# ESP32E_Double_RGB_RevA.net
KiCad netlist of a schematic drawn in EAGLE
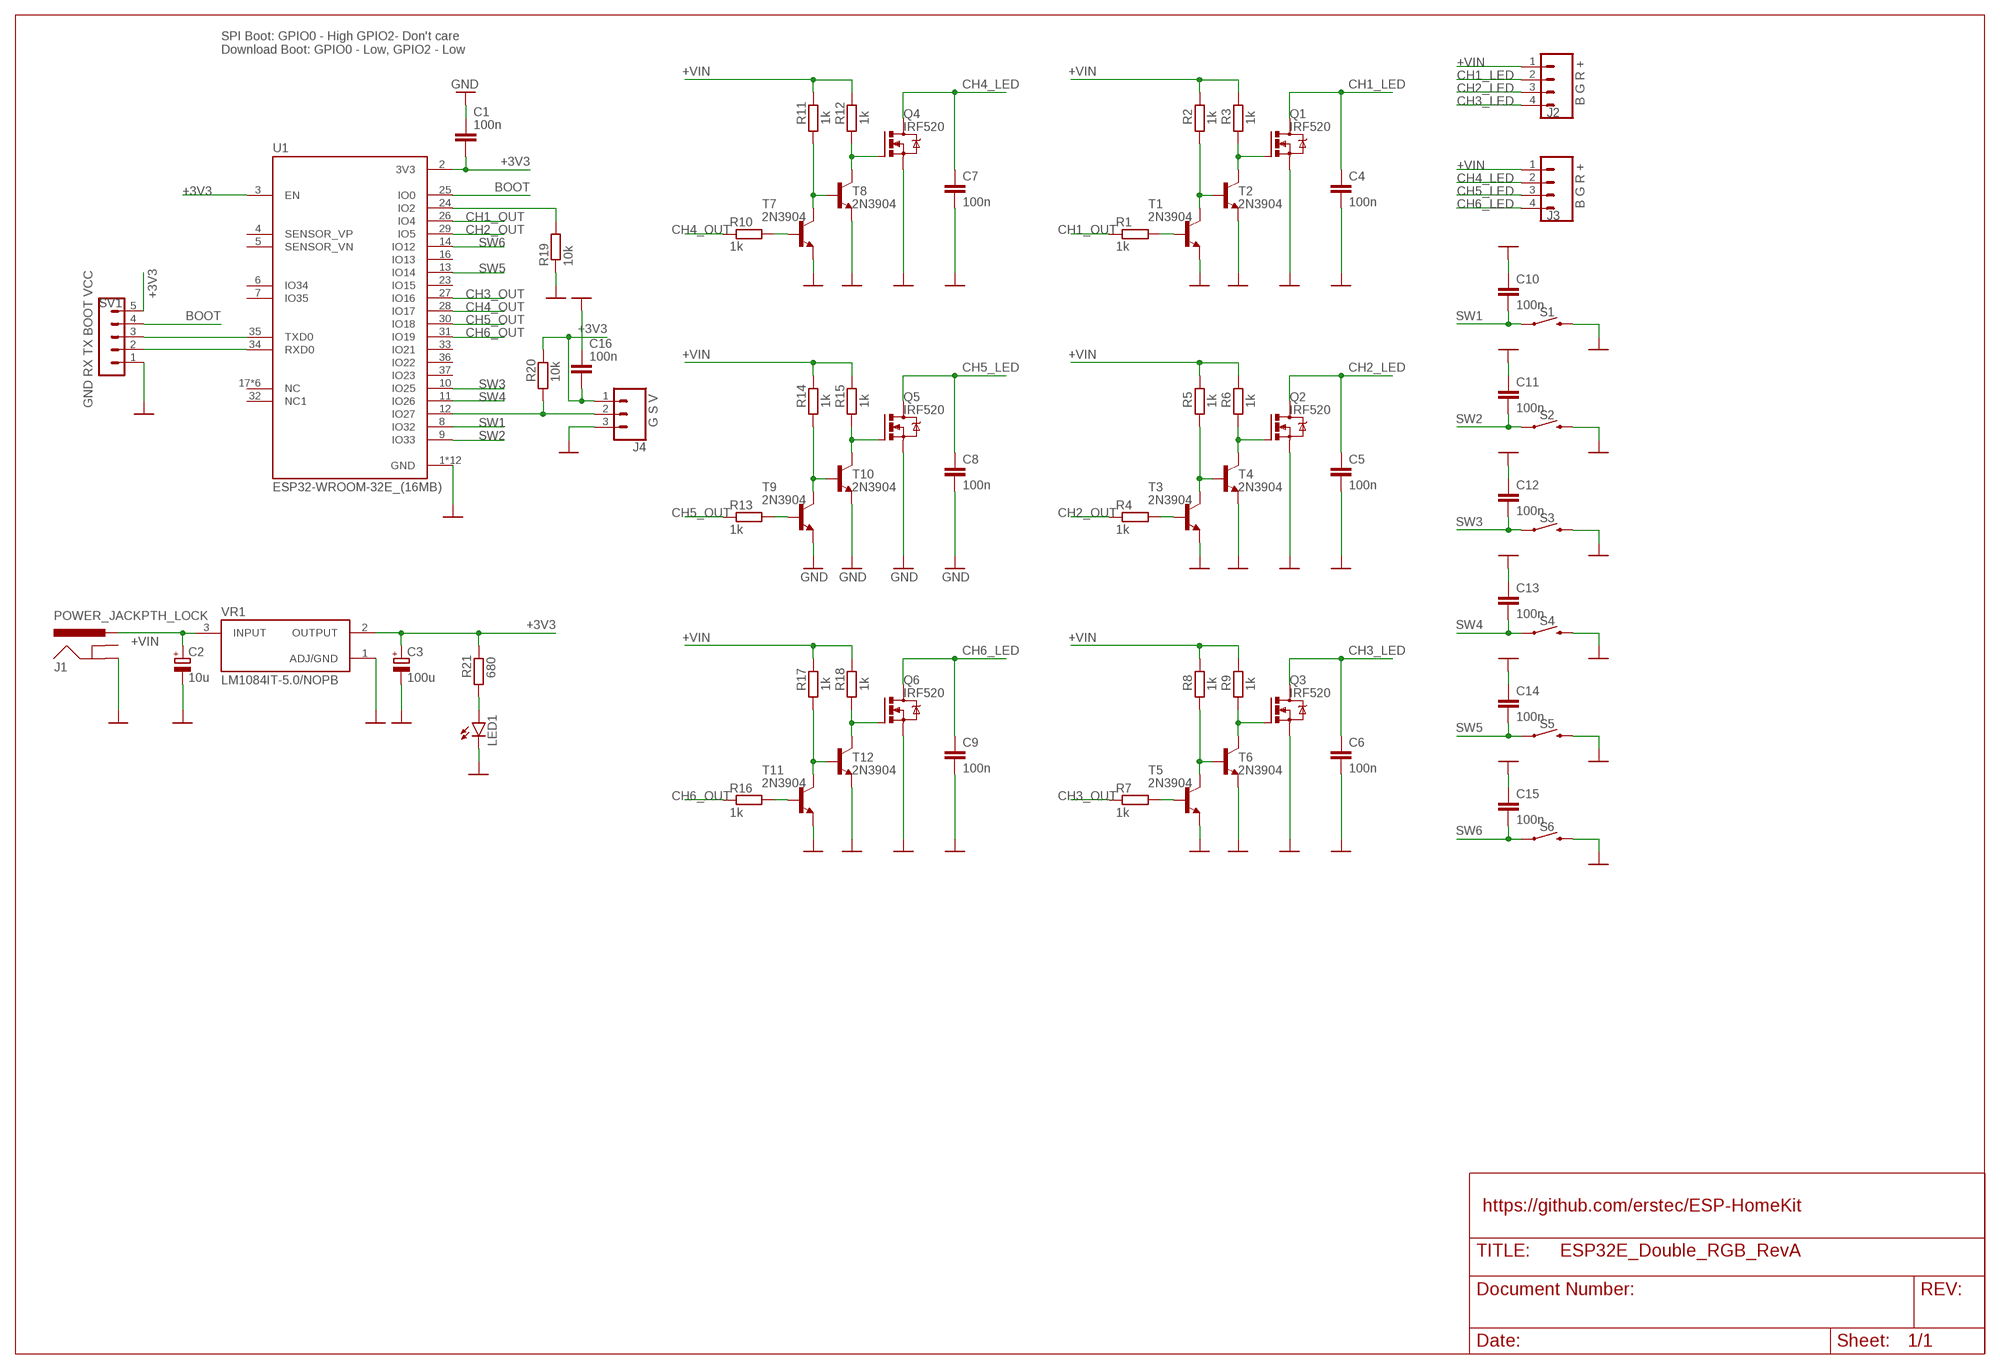
[diagram p0: schematic, sheet 1]

(export (version "E")
  (design (tool "Eeschema 10.0.6"))
  (components
    (comp (ref "C1")
      (value "100n")
      (footprint "eagle-import:C025-024X044")
      (libsource (lib "eagle-import") (part "C-EU025-024X044"))
    )
    (comp (ref "C2")
      (value "10u")
      (footprint "eagle-import:E2,5-6E")
      (libsource (lib "eagle-import") (part "CPOL-EUE2,5-6E"))
    )
    (comp (ref "C3")
      (value "100u")
      (footprint "eagle-import:E2,5-6")
      (libsource (lib "eagle-import") (part "CPOL-EUE2.5-6"))
    )
    (comp (ref "C4")
      (value "100n")
      (footprint "eagle-import:C025-024X044")
      (libsource (lib "eagle-import") (part "C-EU025-024X044"))
    )
    (comp (ref "C5")
      (value "100n")
      (footprint "eagle-import:C025-024X044")
      (libsource (lib "eagle-import") (part "C-EU025-024X044"))
    )
    (comp (ref "C6")
      (value "100n")
      (footprint "eagle-import:C025-024X044")
      (libsource (lib "eagle-import") (part "C-EU025-024X044"))
    )
    (comp (ref "C7")
      (value "100n")
      (footprint "eagle-import:C025-024X044")
      (libsource (lib "eagle-import") (part "C-EU025-024X044"))
    )
    (comp (ref "C8")
      (value "100n")
      (footprint "eagle-import:C025-024X044")
      (libsource (lib "eagle-import") (part "C-EU025-024X044"))
    )
    (comp (ref "C9")
      (value "100n")
      (footprint "eagle-import:C025-024X044")
      (libsource (lib "eagle-import") (part "C-EU025-024X044"))
    )
    (comp (ref "C10")
      (value "100n")
      (footprint "eagle-import:C025-024X044")
      (libsource (lib "eagle-import") (part "C-EU025-024X044"))
    )
    (comp (ref "C11")
      (value "100n")
      (footprint "eagle-import:C025-024X044")
      (libsource (lib "eagle-import") (part "C-EU025-024X044"))
    )
    (comp (ref "C12")
      (value "100n")
      (footprint "eagle-import:C025-024X044")
      (libsource (lib "eagle-import") (part "C-EU025-024X044"))
    )
    (comp (ref "C13")
      (value "100n")
      (footprint "eagle-import:C025-024X044")
      (libsource (lib "eagle-import") (part "C-EU025-024X044"))
    )
    (comp (ref "C14")
      (value "100n")
      (footprint "eagle-import:C025-024X044")
      (libsource (lib "eagle-import") (part "C-EU025-024X044"))
    )
    (comp (ref "C15")
      (value "100n")
      (footprint "eagle-import:C025-024X044")
      (libsource (lib "eagle-import") (part "C-EU025-024X044"))
    )
    (comp (ref "C16")
      (value "100n")
      (footprint "eagle-import:C025-024X044")
      (libsource (lib "eagle-import") (part "C-EU025-024X044"))
    )
    (comp (ref "J1")
      (value "POWER_JACKPTH_LOCK")
      (footprint "eagle-import:POWER_JACK_PTH_LOCK")
      (libsource (lib "eagle-import") (part "POWER_JACKPTH_LOCK"))
    )
    (comp (ref "J2")
      (value "B G R +")
      (footprint "eagle-import:SCREWTERMINAL-3.5MM-4_LOCK")
      (libsource (lib "eagle-import") (part "CONN_04SCREW_LOCK"))
    )
    (comp (ref "J3")
      (value "B G R +")
      (footprint "eagle-import:SCREWTERMINAL-3.5MM-4_LOCK")
      (libsource (lib "eagle-import") (part "CONN_04SCREW_LOCK"))
    )
    (comp (ref "J4")
      (value "G S V")
      (footprint "eagle-import:SCREWTERMINAL-3.5MM-3_LOCK.007S")
      (libsource (lib "eagle-import") (part "CONN_03SCREW_LOCK"))
    )
    (comp (ref "LED1")
      (value "LED5MM")
      (footprint "eagle-import:LED5MM")
      (libsource (lib "eagle-import") (part "LED5MM"))
    )
    (comp (ref "Q1")
      (value "IRF520")
      (footprint "eagle-import:TO220BV")
      (libsource (lib "eagle-import") (part "IRF520"))
    )
    (comp (ref "Q2")
      (value "IRF520")
      (footprint "eagle-import:TO220BV")
      (libsource (lib "eagle-import") (part "IRF520"))
    )
    (comp (ref "Q3")
      (value "IRF520")
      (footprint "eagle-import:TO220BV")
      (libsource (lib "eagle-import") (part "IRF520"))
    )
    (comp (ref "Q4")
      (value "IRF520")
      (footprint "eagle-import:TO220BV")
      (libsource (lib "eagle-import") (part "IRF520"))
    )
    (comp (ref "Q5")
      (value "IRF520")
      (footprint "eagle-import:TO220BV")
      (libsource (lib "eagle-import") (part "IRF520"))
    )
    (comp (ref "Q6")
      (value "IRF520")
      (footprint "eagle-import:TO220BV")
      (libsource (lib "eagle-import") (part "IRF520"))
    )
    (comp (ref "R1")
      (value "1k")
      (footprint "eagle-import:0207_10")
      (libsource (lib "eagle-import") (part "R-EU_0207/10"))
    )
    (comp (ref "R2")
      (value "1k")
      (footprint "eagle-import:0207_10")
      (libsource (lib "eagle-import") (part "R-EU_0207/10"))
    )
    (comp (ref "R3")
      (value "1k")
      (footprint "eagle-import:0207_10")
      (libsource (lib "eagle-import") (part "R-EU_0207/10"))
    )
    (comp (ref "R4")
      (value "1k")
      (footprint "eagle-import:0207_10")
      (libsource (lib "eagle-import") (part "R-EU_0207/10"))
    )
    (comp (ref "R5")
      (value "1k")
      (footprint "eagle-import:0207_10")
      (libsource (lib "eagle-import") (part "R-EU_0207/10"))
    )
    (comp (ref "R6")
      (value "1k")
      (footprint "eagle-import:0207_10")
      (libsource (lib "eagle-import") (part "R-EU_0207/10"))
    )
    (comp (ref "R7")
      (value "1k")
      (footprint "eagle-import:0207_10")
      (libsource (lib "eagle-import") (part "R-EU_0207/10"))
    )
    (comp (ref "R8")
      (value "1k")
      (footprint "eagle-import:0207_10")
      (libsource (lib "eagle-import") (part "R-EU_0207/10"))
    )
    (comp (ref "R9")
      (value "1k")
      (footprint "eagle-import:0207_10")
      (libsource (lib "eagle-import") (part "R-EU_0207/10"))
    )
    (comp (ref "R10")
      (value "1k")
      (footprint "eagle-import:0207_10")
      (libsource (lib "eagle-import") (part "R-EU_0207/10"))
    )
    (comp (ref "R11")
      (value "1k")
      (footprint "eagle-import:0207_10")
      (libsource (lib "eagle-import") (part "R-EU_0207/10"))
    )
    (comp (ref "R12")
      (value "1k")
      (footprint "eagle-import:0207_10")
      (libsource (lib "eagle-import") (part "R-EU_0207/10"))
    )
    (comp (ref "R13")
      (value "1k")
      (footprint "eagle-import:0207_10")
      (libsource (lib "eagle-import") (part "R-EU_0207/10"))
    )
    (comp (ref "R14")
      (value "1k")
      (footprint "eagle-import:0207_10")
      (libsource (lib "eagle-import") (part "R-EU_0207/10"))
    )
    (comp (ref "R15")
      (value "1k")
      (footprint "eagle-import:0207_10")
      (libsource (lib "eagle-import") (part "R-EU_0207/10"))
    )
    (comp (ref "R16")
      (value "1k")
      (footprint "eagle-import:0207_10")
      (libsource (lib "eagle-import") (part "R-EU_0207/10"))
    )
    (comp (ref "R17")
      (value "1k")
      (footprint "eagle-import:0207_10")
      (libsource (lib "eagle-import") (part "R-EU_0207/10"))
    )
    (comp (ref "R18")
      (value "1k")
      (footprint "eagle-import:0207_10")
      (libsource (lib "eagle-import") (part "R-EU_0207/10"))
    )
    (comp (ref "R19")
      (value "10k")
      (footprint "eagle-import:0207_10")
      (libsource (lib "eagle-import") (part "R-EU_0207/10"))
    )
    (comp (ref "R20")
      (value "10k")
      (footprint "eagle-import:0207_10")
      (libsource (lib "eagle-import") (part "R-EU_0207/10"))
    )
    (comp (ref "R21")
      (value "680")
      (footprint "eagle-import:0207_10")
      (libsource (lib "eagle-import") (part "R-EU_0207/10"))
    )
    (comp (ref "S1")
      (value "MOMENTARY-SWITCH-SPST-PTH-6.0MM")
      (footprint "eagle-import:TACTILE_SWITCH_PTH_6.0MM")
      (libsource (lib "eagle-import") (part "MOMENTARY-SWITCH-SPST-PTH-6.0MM"))
    )
    (comp (ref "S2")
      (value "MOMENTARY-SWITCH-SPST-PTH-6.0MM")
      (footprint "eagle-import:TACTILE_SWITCH_PTH_6.0MM")
      (libsource (lib "eagle-import") (part "MOMENTARY-SWITCH-SPST-PTH-6.0MM"))
    )
    (comp (ref "S3")
      (value "MOMENTARY-SWITCH-SPST-PTH-6.0MM")
      (footprint "eagle-import:TACTILE_SWITCH_PTH_6.0MM")
      (libsource (lib "eagle-import") (part "MOMENTARY-SWITCH-SPST-PTH-6.0MM"))
    )
    (comp (ref "S4")
      (value "MOMENTARY-SWITCH-SPST-PTH-6.0MM")
      (footprint "eagle-import:TACTILE_SWITCH_PTH_6.0MM")
      (libsource (lib "eagle-import") (part "MOMENTARY-SWITCH-SPST-PTH-6.0MM"))
    )
    (comp (ref "S5")
      (value "MOMENTARY-SWITCH-SPST-PTH-6.0MM")
      (footprint "eagle-import:TACTILE_SWITCH_PTH_6.0MM")
      (libsource (lib "eagle-import") (part "MOMENTARY-SWITCH-SPST-PTH-6.0MM"))
    )
    (comp (ref "S6")
      (value "MOMENTARY-SWITCH-SPST-PTH-6.0MM")
      (footprint "eagle-import:TACTILE_SWITCH_PTH_6.0MM")
      (libsource (lib "eagle-import") (part "MOMENTARY-SWITCH-SPST-PTH-6.0MM"))
    )
    (comp (ref "SV1")
      (value "GND RX TX BOOT VCC")
      (footprint "eagle-import:MA05-1")
      (libsource (lib "eagle-import") (part "MA05-1"))
    )
    (comp (ref "T1")
      (value "2N3904")
      (footprint "eagle-import:TO92")
      (libsource (lib "eagle-import") (part "2N3904"))
    )
    (comp (ref "T2")
      (value "2N3904")
      (footprint "eagle-import:TO92")
      (libsource (lib "eagle-import") (part "2N3904"))
    )
    (comp (ref "T3")
      (value "2N3904")
      (footprint "eagle-import:TO92")
      (libsource (lib "eagle-import") (part "2N3904"))
    )
    (comp (ref "T4")
      (value "2N3904")
      (footprint "eagle-import:TO92")
      (libsource (lib "eagle-import") (part "2N3904"))
    )
    (comp (ref "T5")
      (value "2N3904")
      (footprint "eagle-import:TO92")
      (libsource (lib "eagle-import") (part "2N3904"))
    )
    (comp (ref "T6")
      (value "2N3904")
      (footprint "eagle-import:TO92")
      (libsource (lib "eagle-import") (part "2N3904"))
    )
    (comp (ref "T7")
      (value "2N3904")
      (footprint "eagle-import:TO92")
      (libsource (lib "eagle-import") (part "2N3904"))
    )
    (comp (ref "T8")
      (value "2N3904")
      (footprint "eagle-import:TO92")
      (libsource (lib "eagle-import") (part "2N3904"))
    )
    (comp (ref "T9")
      (value "2N3904")
      (footprint "eagle-import:TO92")
      (libsource (lib "eagle-import") (part "2N3904"))
    )
    (comp (ref "T10")
      (value "2N3904")
      (footprint "eagle-import:TO92")
      (libsource (lib "eagle-import") (part "2N3904"))
    )
    (comp (ref "T11")
      (value "2N3904")
      (footprint "eagle-import:TO92")
      (libsource (lib "eagle-import") (part "2N3904"))
    )
    (comp (ref "T12")
      (value "2N3904")
      (footprint "eagle-import:TO92")
      (libsource (lib "eagle-import") (part "2N3904"))
    )
    (comp (ref "U1")
      (value "ESP32-WROOM-32E_(16MB)")
      (footprint "eagle-import:XCVR_ESP32-WROOM-32E_(16MB)")
      (fields (field (name "MF") "Espressif Systems") (field (name "MP") "ESP32-WROOM-32E (16MB)"))
      (libsource (lib "eagle-import") (part "ESP32-WROOM-32E_(16MB)"))
    )
    (comp (ref "VR1")
      (value "LM1084IT-5.0/NOPB")
      (footprint "eagle-import:TO254P1054X470X1955-3")
      (fields (field (name "MF") "Texas Instruments"))
      (libsource (lib "eagle-import") (part "LM1084IT-5.0/NOPB"))
    )
  )
  (nets
    (net (code "1") (name "/+3V3") (class "Default")
      (node (ref "C1") (pin "2") (pinfunction "2_2") (pintype "passive"))
      (node (ref "C16") (pin "2") (pinfunction "2_2") (pintype "passive"))
      (node (ref "C3") (pin "+") (pinfunction "+_+") (pintype "passive"))
      (node (ref "J4") (pin "1") (pinfunction "1_1") (pintype "passive"))
      (node (ref "R20") (pin "2") (pinfunction "2_2") (pintype "passive"))
      (node (ref "R21") (pin "2") (pinfunction "2_2") (pintype "passive"))
      (node (ref "SV1") (pin "5") (pinfunction "5_5") (pintype "passive"))
      (node (ref "U1") (pin "2") (pinfunction "3V3_2") (pintype "power_in"))
      (node (ref "U1") (pin "3") (pinfunction "EN_3") (pintype "input"))
      (node (ref "VR1") (pin "2") (pinfunction "OUTPUT_2") (pintype "output"))
    )
    (net (code "2") (name "/+VIN") (class "Default")
      (node (ref "C2") (pin "+") (pinfunction "+_+") (pintype "passive"))
      (node (ref "J1") (pin "PWR") (pinfunction "PWR_PWR") (pintype "bidirectional"))
      (node (ref "J2") (pin "1") (pinfunction "1_1") (pintype "passive"))
      (node (ref "J3") (pin "1") (pinfunction "1_1") (pintype "passive"))
      (node (ref "R11") (pin "2") (pinfunction "2_2") (pintype "passive"))
      (node (ref "R12") (pin "2") (pinfunction "2_2") (pintype "passive"))
      (node (ref "R14") (pin "2") (pinfunction "2_2") (pintype "passive"))
      (node (ref "R15") (pin "2") (pinfunction "2_2") (pintype "passive"))
      (node (ref "R17") (pin "2") (pinfunction "2_2") (pintype "passive"))
      (node (ref "R18") (pin "2") (pinfunction "2_2") (pintype "passive"))
      (node (ref "R2") (pin "2") (pinfunction "2_2") (pintype "passive"))
      (node (ref "R3") (pin "2") (pinfunction "2_2") (pintype "passive"))
      (node (ref "R5") (pin "2") (pinfunction "2_2") (pintype "passive"))
      (node (ref "R6") (pin "2") (pinfunction "2_2") (pintype "passive"))
      (node (ref "R8") (pin "2") (pinfunction "2_2") (pintype "passive"))
      (node (ref "R9") (pin "2") (pinfunction "2_2") (pintype "passive"))
      (node (ref "VR1") (pin "3") (pinfunction "INPUT_3") (pintype "input"))
    )
    (net (code "3") (name "/BOOT") (class "Default")
      (node (ref "SV1") (pin "4") (pinfunction "4_4") (pintype "passive"))
      (node (ref "U1") (pin "25") (pinfunction "IO0_25") (pintype "bidirectional"))
    )
    (net (code "4") (name "/CH1_LED") (class "Default")
      (node (ref "C4") (pin "1") (pinfunction "1_1") (pintype "passive"))
      (node (ref "J2") (pin "2") (pinfunction "2_2") (pintype "passive"))
      (node (ref "Q1") (pin "D") (pinfunction "D_D") (pintype "passive"))
    )
    (net (code "5") (name "/CH1_OUT") (class "Default")
      (node (ref "R1") (pin "1") (pinfunction "1_1") (pintype "passive"))
      (node (ref "U1") (pin "26") (pinfunction "IO4_26") (pintype "bidirectional"))
    )
    (net (code "6") (name "/CH2_LED") (class "Default")
      (node (ref "C5") (pin "1") (pinfunction "1_1") (pintype "passive"))
      (node (ref "J2") (pin "3") (pinfunction "3_3") (pintype "passive"))
      (node (ref "Q2") (pin "D") (pinfunction "D_D") (pintype "passive"))
    )
    (net (code "7") (name "/CH2_OUT") (class "Default")
      (node (ref "R4") (pin "1") (pinfunction "1_1") (pintype "passive"))
      (node (ref "U1") (pin "29") (pinfunction "IO5_29") (pintype "bidirectional"))
    )
    (net (code "8") (name "/CH3_LED") (class "Default")
      (node (ref "C6") (pin "1") (pinfunction "1_1") (pintype "passive"))
      (node (ref "J2") (pin "4") (pinfunction "4_4") (pintype "passive"))
      (node (ref "Q3") (pin "D") (pinfunction "D_D") (pintype "passive"))
    )
    (net (code "9") (name "/CH3_OUT") (class "Default")
      (node (ref "R7") (pin "1") (pinfunction "1_1") (pintype "passive"))
      (node (ref "U1") (pin "27") (pinfunction "IO16_27") (pintype "bidirectional"))
    )
    (net (code "10") (name "/CH4_LED") (class "Default")
      (node (ref "C7") (pin "1") (pinfunction "1_1") (pintype "passive"))
      (node (ref "J3") (pin "2") (pinfunction "2_2") (pintype "passive"))
      (node (ref "Q4") (pin "D") (pinfunction "D_D") (pintype "passive"))
    )
    (net (code "11") (name "/CH4_OUT") (class "Default")
      (node (ref "R10") (pin "1") (pinfunction "1_1") (pintype "passive"))
      (node (ref "U1") (pin "28") (pinfunction "IO17_28") (pintype "bidirectional"))
    )
    (net (code "12") (name "/CH5_LED") (class "Default")
      (node (ref "C8") (pin "1") (pinfunction "1_1") (pintype "passive"))
      (node (ref "J3") (pin "3") (pinfunction "3_3") (pintype "passive"))
      (node (ref "Q5") (pin "D") (pinfunction "D_D") (pintype "passive"))
    )
    (net (code "13") (name "/CH5_OUT") (class "Default")
      (node (ref "R13") (pin "1") (pinfunction "1_1") (pintype "passive"))
      (node (ref "U1") (pin "30") (pinfunction "IO18_30") (pintype "bidirectional"))
    )
    (net (code "14") (name "/CH6_LED") (class "Default")
      (node (ref "C9") (pin "1") (pinfunction "1_1") (pintype "passive"))
      (node (ref "J3") (pin "4") (pinfunction "4_4") (pintype "passive"))
      (node (ref "Q6") (pin "D") (pinfunction "D_D") (pintype "passive"))
    )
    (net (code "15") (name "/CH6_OUT") (class "Default")
      (node (ref "R16") (pin "1") (pinfunction "1_1") (pintype "passive"))
      (node (ref "U1") (pin "31") (pinfunction "IO19_31") (pintype "bidirectional"))
    )
    (net (code "16") (name "/SW1") (class "Default")
      (node (ref "C10") (pin "2") (pinfunction "2_2") (pintype "passive"))
      (node (ref "S1") (pin "1") (pinfunction "1_1") (pintype "passive"))
      (node (ref "U1") (pin "8") (pinfunction "IO32_8") (pintype "bidirectional"))
    )
    (net (code "17") (name "/SW2") (class "Default")
      (node (ref "C11") (pin "2") (pinfunction "2_2") (pintype "passive"))
      (node (ref "S2") (pin "1") (pinfunction "1_1") (pintype "passive"))
      (node (ref "U1") (pin "9") (pinfunction "IO33_9") (pintype "bidirectional"))
    )
    (net (code "18") (name "/SW3") (class "Default")
      (node (ref "C12") (pin "2") (pinfunction "2_2") (pintype "passive"))
      (node (ref "S3") (pin "1") (pinfunction "1_1") (pintype "passive"))
      (node (ref "U1") (pin "10") (pinfunction "IO25_10") (pintype "bidirectional"))
    )
    (net (code "19") (name "/SW4") (class "Default")
      (node (ref "C13") (pin "2") (pinfunction "2_2") (pintype "passive"))
      (node (ref "S4") (pin "1") (pinfunction "1_1") (pintype "passive"))
      (node (ref "U1") (pin "11") (pinfunction "IO26_11") (pintype "bidirectional"))
    )
    (net (code "20") (name "/SW5") (class "Default")
      (node (ref "C14") (pin "2") (pinfunction "2_2") (pintype "passive"))
      (node (ref "S5") (pin "1") (pinfunction "1_1") (pintype "passive"))
      (node (ref "U1") (pin "13") (pinfunction "IO14_13") (pintype "bidirectional"))
    )
    (net (code "21") (name "/SW6") (class "Default")
      (node (ref "C15") (pin "2") (pinfunction "2_2") (pintype "passive"))
      (node (ref "S6") (pin "1") (pinfunction "1_1") (pintype "passive"))
      (node (ref "U1") (pin "14") (pinfunction "IO12_14") (pintype "bidirectional"))
    )
    (net (code "22") (name "GND") (class "Default")
      (node (ref "C1") (pin "1") (pinfunction "1_1") (pintype "passive"))
      (node (ref "C10") (pin "1") (pinfunction "1_1") (pintype "passive"))
      (node (ref "C11") (pin "1") (pinfunction "1_1") (pintype "passive"))
      (node (ref "C12") (pin "1") (pinfunction "1_1") (pintype "passive"))
      (node (ref "C13") (pin "1") (pinfunction "1_1") (pintype "passive"))
      (node (ref "C14") (pin "1") (pinfunction "1_1") (pintype "passive"))
      (node (ref "C15") (pin "1") (pinfunction "1_1") (pintype "passive"))
      (node (ref "C16") (pin "1") (pinfunction "1_1") (pintype "passive"))
      (node (ref "C2") (pin "-") (pinfunction "-_-") (pintype "passive"))
      (node (ref "C3") (pin "-") (pinfunction "-_-") (pintype "passive"))
      (node (ref "C4") (pin "2") (pinfunction "2_2") (pintype "passive"))
      (node (ref "C5") (pin "2") (pinfunction "2_2") (pintype "passive"))
      (node (ref "C6") (pin "2") (pinfunction "2_2") (pintype "passive"))
      (node (ref "C7") (pin "2") (pinfunction "2_2") (pintype "passive"))
      (node (ref "C8") (pin "2") (pinfunction "2_2") (pintype "passive"))
      (node (ref "C9") (pin "2") (pinfunction "2_2") (pintype "passive"))
      (node (ref "J1") (pin "GND") (pinfunction "GND_GND") (pintype "bidirectional"))
      (node (ref "J4") (pin "3") (pinfunction "3_3") (pintype "passive"))
      (node (ref "LED1") (pin "K") (pinfunction "C_K") (pintype "passive"))
      (node (ref "Q1") (pin "S") (pinfunction "S_S") (pintype "passive"))
      (node (ref "Q2") (pin "S") (pinfunction "S_S") (pintype "passive"))
      (node (ref "Q3") (pin "S") (pinfunction "S_S") (pintype "passive"))
      (node (ref "Q4") (pin "S") (pinfunction "S_S") (pintype "passive"))
      (node (ref "Q5") (pin "S") (pinfunction "S_S") (pintype "passive"))
      (node (ref "Q6") (pin "S") (pinfunction "S_S") (pintype "passive"))
      (node (ref "R19") (pin "1") (pinfunction "1_1") (pintype "passive"))
      (node (ref "S1") (pin "3") (pinfunction "2_3") (pintype "passive"))
      (node (ref "S2") (pin "3") (pinfunction "2_3") (pintype "passive"))
      (node (ref "S3") (pin "3") (pinfunction "2_3") (pintype "passive"))
      (node (ref "S4") (pin "3") (pinfunction "2_3") (pintype "passive"))
      (node (ref "S5") (pin "3") (pinfunction "2_3") (pintype "passive"))
      (node (ref "S6") (pin "3") (pinfunction "2_3") (pintype "passive"))
      (node (ref "SV1") (pin "1") (pinfunction "1_1") (pintype "passive"))
      (node (ref "T1") (pin "3") (pinfunction "E_3") (pintype "passive"))
      (node (ref "T10") (pin "3") (pinfunction "E_3") (pintype "passive"))
      (node (ref "T11") (pin "3") (pinfunction "E_3") (pintype "passive"))
      (node (ref "T12") (pin "3") (pinfunction "E_3") (pintype "passive"))
      (node (ref "T2") (pin "3") (pinfunction "E_3") (pintype "passive"))
      (node (ref "T3") (pin "3") (pinfunction "E_3") (pintype "passive"))
      (node (ref "T4") (pin "3") (pinfunction "E_3") (pintype "passive"))
      (node (ref "T5") (pin "3") (pinfunction "E_3") (pintype "passive"))
      (node (ref "T6") (pin "3") (pinfunction "E_3") (pintype "passive"))
      (node (ref "T7") (pin "3") (pinfunction "E_3") (pintype "passive"))
      (node (ref "T8") (pin "3") (pinfunction "E_3") (pintype "passive"))
      (node (ref "T9") (pin "3") (pinfunction "E_3") (pintype "passive"))
      (node (ref "U1") (pin "1") (pinfunction "GND_1") (pintype "power_in"))
      (node (ref "U1") (pin "15") (pinfunction "GND_15") (pintype "power_in"))
      (node (ref "U1") (pin "38") (pinfunction "GND_38") (pintype "power_in"))
      (node (ref "U1") (pin "39_1") (pinfunction "GND_39_1") (pintype "power_in"))
      (node (ref "U1") (pin "39_2") (pinfunction "GND_39_2") (pintype "power_in"))
      (node (ref "U1") (pin "39_3") (pinfunction "GND_39_3") (pintype "power_in"))
      (node (ref "U1") (pin "39_4") (pinfunction "GND_39_4") (pintype "power_in"))
      (node (ref "U1") (pin "39_5") (pinfunction "GND_39_5") (pintype "power_in"))
      (node (ref "U1") (pin "39_6") (pinfunction "GND_39_6") (pintype "power_in"))
      (node (ref "U1") (pin "39_7") (pinfunction "GND_39_7") (pintype "power_in"))
      (node (ref "U1") (pin "39_8") (pinfunction "GND_39_8") (pintype "power_in"))
      (node (ref "U1") (pin "39_9") (pinfunction "GND_39_9") (pintype "power_in"))
      (node (ref "VR1") (pin "1") (pinfunction "ADJ/GND_1") (pintype "power_in"))
    )
    (net (code "23") (name "Net-(LED1-PadA)") (class "Default")
      (node (ref "LED1") (pin "A") (pinfunction "A_A") (pintype "passive"))
      (node (ref "R21") (pin "1") (pinfunction "1_1") (pintype "passive"))
    )
    (net (code "24") (name "Net-(T1-B)") (class "Default")
      (node (ref "R1") (pin "2") (pinfunction "2_2") (pintype "passive"))
      (node (ref "T1") (pin "2") (pinfunction "B_2") (pintype "passive"))
    )
    (net (code "25") (name "Net-(T1-C)") (class "Default")
      (node (ref "R2") (pin "1") (pinfunction "1_1") (pintype "passive"))
      (node (ref "T1") (pin "1") (pinfunction "C_1") (pintype "passive"))
      (node (ref "T2") (pin "2") (pinfunction "B_2") (pintype "passive"))
    )
    (net (code "26") (name "Net-(T2-C)") (class "Default")
      (node (ref "Q1") (pin "G") (pinfunction "G_G") (pintype "passive"))
      (node (ref "R3") (pin "1") (pinfunction "1_1") (pintype "passive"))
      (node (ref "T2") (pin "1") (pinfunction "C_1") (pintype "passive"))
    )
    (net (code "27") (name "Net-(T3-B)") (class "Default")
      (node (ref "R4") (pin "2") (pinfunction "2_2") (pintype "passive"))
      (node (ref "T3") (pin "2") (pinfunction "B_2") (pintype "passive"))
    )
    (net (code "28") (name "Net-(T3-C)") (class "Default")
      (node (ref "R5") (pin "1") (pinfunction "1_1") (pintype "passive"))
      (node (ref "T3") (pin "1") (pinfunction "C_1") (pintype "passive"))
      (node (ref "T4") (pin "2") (pinfunction "B_2") (pintype "passive"))
    )
    (net (code "29") (name "Net-(T4-C)") (class "Default")
      (node (ref "Q2") (pin "G") (pinfunction "G_G") (pintype "passive"))
      (node (ref "R6") (pin "1") (pinfunction "1_1") (pintype "passive"))
      (node (ref "T4") (pin "1") (pinfunction "C_1") (pintype "passive"))
    )
    (net (code "30") (name "Net-(T5-B)") (class "Default")
      (node (ref "R7") (pin "2") (pinfunction "2_2") (pintype "passive"))
      (node (ref "T5") (pin "2") (pinfunction "B_2") (pintype "passive"))
    )
    (net (code "31") (name "Net-(T5-C)") (class "Default")
      (node (ref "R8") (pin "1") (pinfunction "1_1") (pintype "passive"))
      (node (ref "T5") (pin "1") (pinfunction "C_1") (pintype "passive"))
      (node (ref "T6") (pin "2") (pinfunction "B_2") (pintype "passive"))
    )
    (net (code "32") (name "Net-(T6-C)") (class "Default")
      (node (ref "Q3") (pin "G") (pinfunction "G_G") (pintype "passive"))
      (node (ref "R9") (pin "1") (pinfunction "1_1") (pintype "passive"))
      (node (ref "T6") (pin "1") (pinfunction "C_1") (pintype "passive"))
    )
    (net (code "33") (name "Net-(T7-B)") (class "Default")
      (node (ref "R10") (pin "2") (pinfunction "2_2") (pintype "passive"))
      (node (ref "T7") (pin "2") (pinfunction "B_2") (pintype "passive"))
    )
    (net (code "34") (name "Net-(T7-C)") (class "Default")
      (node (ref "R11") (pin "1") (pinfunction "1_1") (pintype "passive"))
      (node (ref "T7") (pin "1") (pinfunction "C_1") (pintype "passive"))
      (node (ref "T8") (pin "2") (pinfunction "B_2") (pintype "passive"))
    )
    (net (code "35") (name "Net-(T8-C)") (class "Default")
      (node (ref "Q4") (pin "G") (pinfunction "G_G") (pintype "passive"))
      (node (ref "R12") (pin "1") (pinfunction "1_1") (pintype "passive"))
      (node (ref "T8") (pin "1") (pinfunction "C_1") (pintype "passive"))
    )
    (net (code "36") (name "Net-(T9-B)") (class "Default")
      (node (ref "R13") (pin "2") (pinfunction "2_2") (pintype "passive"))
      (node (ref "T9") (pin "2") (pinfunction "B_2") (pintype "passive"))
    )
    (net (code "37") (name "Net-(T10-B)") (class "Default")
      (node (ref "R14") (pin "1") (pinfunction "1_1") (pintype "passive"))
      (node (ref "T10") (pin "2") (pinfunction "B_2") (pintype "passive"))
      (node (ref "T9") (pin "1") (pinfunction "C_1") (pintype "passive"))
    )
    (net (code "38") (name "Net-(T10-C)") (class "Default")
      (node (ref "Q5") (pin "G") (pinfunction "G_G") (pintype "passive"))
      (node (ref "R15") (pin "1") (pinfunction "1_1") (pintype "passive"))
      (node (ref "T10") (pin "1") (pinfunction "C_1") (pintype "passive"))
    )
    (net (code "39") (name "Net-(T11-B)") (class "Default")
      (node (ref "R16") (pin "2") (pinfunction "2_2") (pintype "passive"))
      (node (ref "T11") (pin "2") (pinfunction "B_2") (pintype "passive"))
    )
    (net (code "40") (name "Net-(T11-C)") (class "Default")
      (node (ref "R17") (pin "1") (pinfunction "1_1") (pintype "passive"))
      (node (ref "T11") (pin "1") (pinfunction "C_1") (pintype "passive"))
      (node (ref "T12") (pin "2") (pinfunction "B_2") (pintype "passive"))
    )
    (net (code "41") (name "Net-(T12-C)") (class "Default")
      (node (ref "Q6") (pin "G") (pinfunction "G_G") (pintype "passive"))
      (node (ref "R18") (pin "1") (pinfunction "1_1") (pintype "passive"))
      (node (ref "T12") (pin "1") (pinfunction "C_1") (pintype "passive"))
    )
    (net (code "42") (name "Net-(U1-IO2)") (class "Default")
      (node (ref "R19") (pin "2") (pinfunction "2_2") (pintype "passive"))
      (node (ref "U1") (pin "24") (pinfunction "IO2_24") (pintype "bidirectional"))
    )
    (net (code "43") (name "Net-(U1-IO27)") (class "Default")
      (node (ref "J4") (pin "2") (pinfunction "2_2") (pintype "passive"))
      (node (ref "R20") (pin "1") (pinfunction "1_1") (pintype "passive"))
      (node (ref "U1") (pin "12") (pinfunction "IO27_12") (pintype "bidirectional"))
    )
    (net (code "44") (name "Net-(U1-RXD0)") (class "Default")
      (node (ref "SV1") (pin "2") (pinfunction "2_2") (pintype "passive"))
      (node (ref "U1") (pin "34") (pinfunction "RXD0_34") (pintype "bidirectional"))
    )
    (net (code "45") (name "Net-(U1-TXD0)") (class "Default")
      (node (ref "SV1") (pin "3") (pinfunction "3_3") (pintype "passive"))
      (node (ref "U1") (pin "35") (pinfunction "TXD0_35") (pintype "bidirectional"))
    )
    (net (code "46") (name "unconnected-(J1-PadGNDBREAK)") (class "Default")
      (node (ref "J1") (pin "GNDBREAK") (pinfunction "GNDBREAK_GNDBREAK") (pintype "bidirectional"))
    )
    (net (code "47") (name "unconnected-(U1-IO13-Pad16)") (class "Default")
      (node (ref "U1") (pin "16") (pinfunction "IO13_16") (pintype "bidirectional"))
    )
    (net (code "48") (name "unconnected-(U1-IO15-Pad23)") (class "Default")
      (node (ref "U1") (pin "23") (pinfunction "IO15_23") (pintype "bidirectional"))
    )
    (net (code "49") (name "unconnected-(U1-IO21-Pad33)") (class "Default")
      (node (ref "U1") (pin "33") (pinfunction "IO21_33") (pintype "bidirectional"))
    )
    (net (code "50") (name "unconnected-(U1-IO22-Pad36)") (class "Default")
      (node (ref "U1") (pin "36") (pinfunction "IO22_36") (pintype "bidirectional"))
    )
    (net (code "51") (name "unconnected-(U1-IO23-Pad37)") (class "Default")
      (node (ref "U1") (pin "37") (pinfunction "IO23_37") (pintype "bidirectional"))
    )
    (net (code "52") (name "unconnected-(U1-IO34-Pad6)") (class "Default")
      (node (ref "U1") (pin "6") (pinfunction "IO34_6") (pintype "input"))
    )
    (net (code "53") (name "unconnected-(U1-IO35-Pad7)") (class "Default")
      (node (ref "U1") (pin "7") (pinfunction "IO35_7") (pintype "input"))
    )
    (net (code "54") (name "unconnected-(U1-NC-Pad17)") (class "Default")
      (node (ref "U1") (pin "17") (pinfunction "NC_17") (pintype "no_connect"))
    )
    (net (code "55") (name "unconnected-(U1-NC-Pad18)") (class "Default")
      (node (ref "U1") (pin "18") (pinfunction "NC_18") (pintype "no_connect"))
    )
    (net (code "56") (name "unconnected-(U1-NC-Pad19)") (class "Default")
      (node (ref "U1") (pin "19") (pinfunction "NC_19") (pintype "no_connect"))
    )
    (net (code "57") (name "unconnected-(U1-NC-Pad20)") (class "Default")
      (node (ref "U1") (pin "20") (pinfunction "NC_20") (pintype "no_connect"))
    )
    (net (code "58") (name "unconnected-(U1-NC-Pad21)") (class "Default")
      (node (ref "U1") (pin "21") (pinfunction "NC_21") (pintype "no_connect"))
    )
    (net (code "59") (name "unconnected-(U1-NC-Pad22)") (class "Default")
      (node (ref "U1") (pin "22") (pinfunction "NC_22") (pintype "no_connect"))
    )
    (net (code "60") (name "unconnected-(U1-NC1-Pad32)") (class "Default")
      (node (ref "U1") (pin "32") (pinfunction "NC1_32") (pintype "no_connect"))
    )
    (net (code "61") (name "unconnected-(U1-SENSOR_VN-Pad5)") (class "Default")
      (node (ref "U1") (pin "5") (pinfunction "SENSOR_VN_5") (pintype "input"))
    )
    (net (code "62") (name "unconnected-(U1-SENSOR_VP-Pad4)") (class "Default")
      (node (ref "U1") (pin "4") (pinfunction "SENSOR_VP_4") (pintype "input"))
    )
  )
)
